# STM32_esc.net
KiCad netlist of a schematic drawn in EAGLE
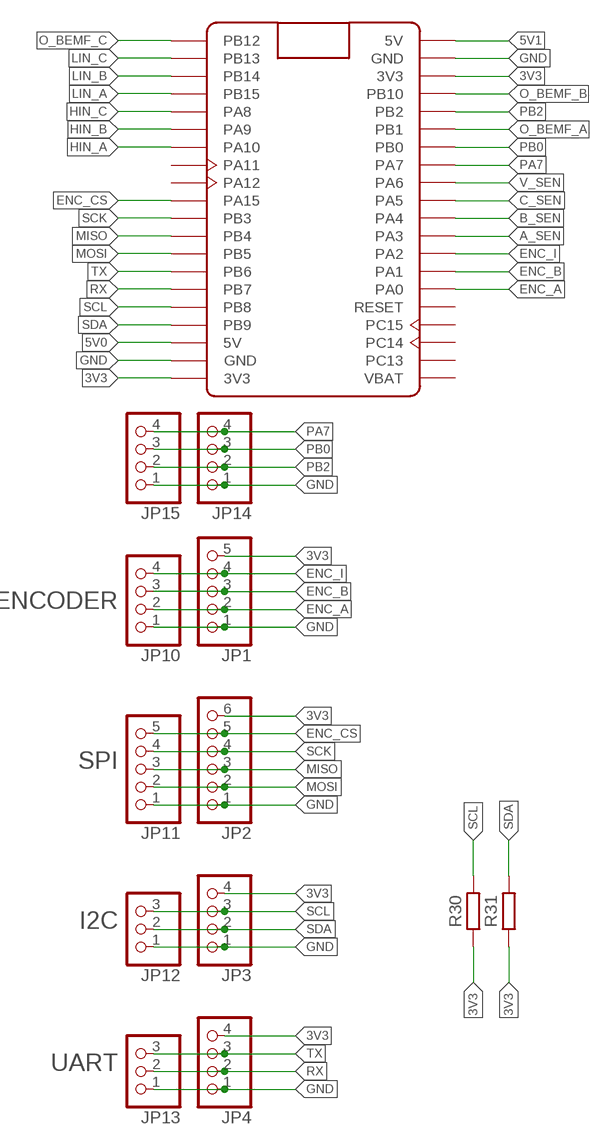
[diagram p0: schematic, sheet 1, part 1 of 2]
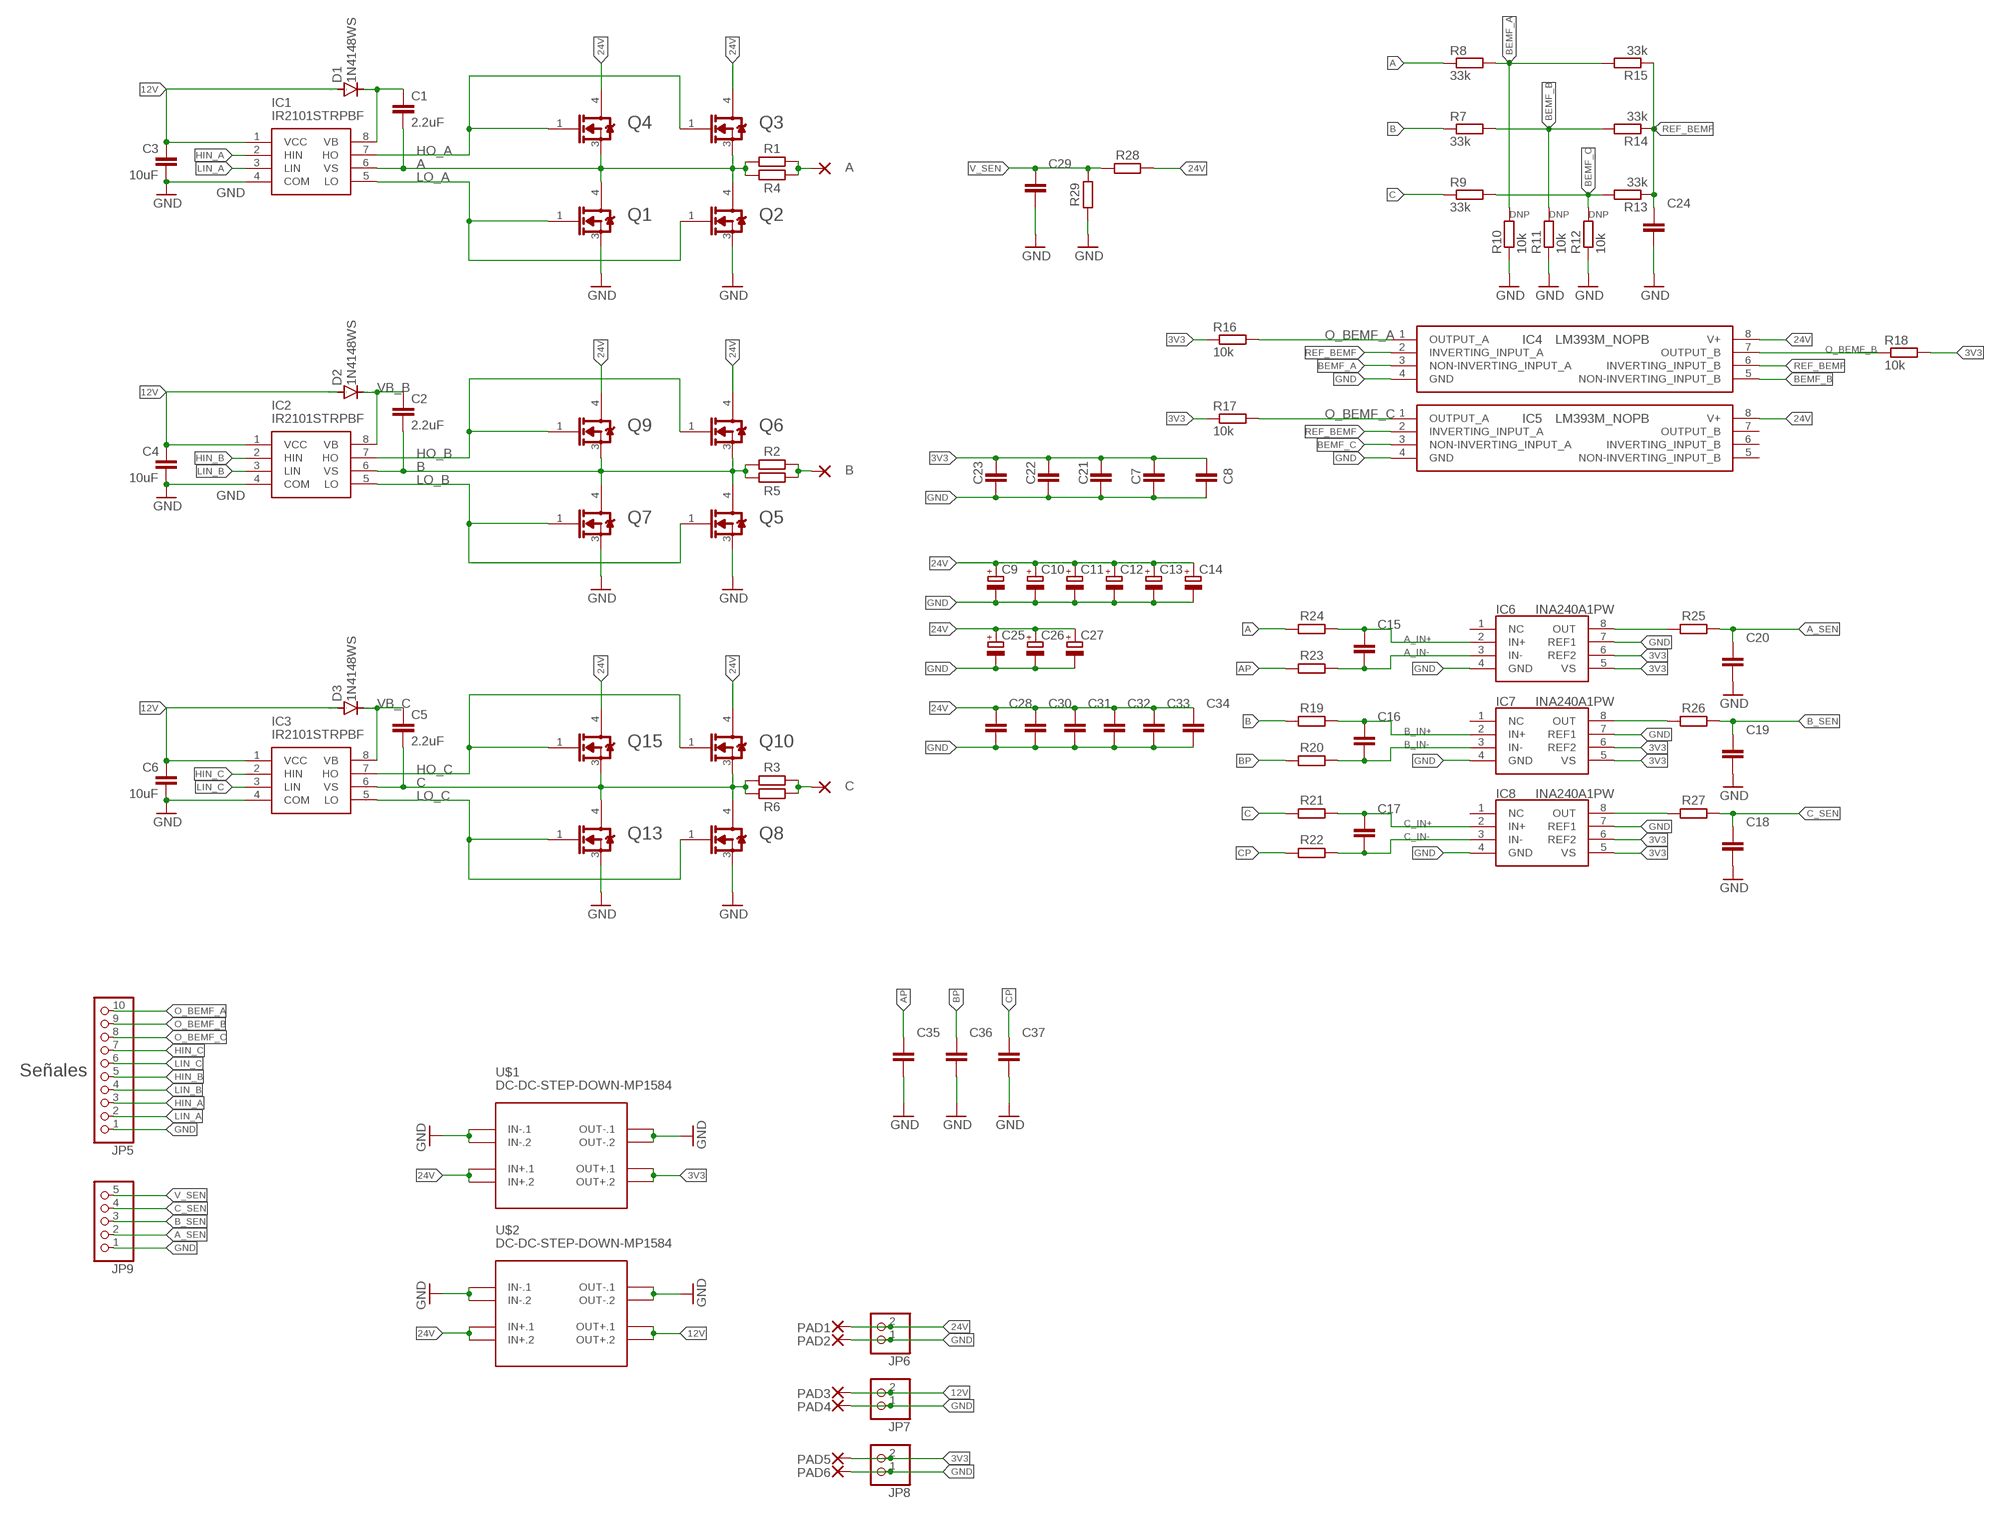
[diagram p1: schematic, sheet 1, part 2 of 2]

(export (version "E")
  (design (tool "Eeschema 10.0.6"))
  (components
    (comp (ref "A")
      (value "SMD5")
      (footprint "eagle-import:SMD2,54-5,08")
      (libsource (lib "eagle-import") (part "SMD5"))
    )
    (comp (ref "B")
      (value "SMD5")
      (footprint "eagle-import:SMD2,54-5,08")
      (libsource (lib "eagle-import") (part "SMD5"))
    )
    (comp (ref "C")
      (value "SMD5")
      (footprint "eagle-import:SMD2,54-5,08")
      (libsource (lib "eagle-import") (part "SMD5"))
    )
    (comp (ref "C1")
      (value "2.2uF")
      (footprint "eagle-import:CAPC3216X135")
      (libsource (lib "eagle-import") (part "CCHIP-1206(3216-METRIC)_"))
    )
    (comp (ref "C2")
      (value "2.2uF")
      (footprint "eagle-import:CAPC3216X135")
      (libsource (lib "eagle-import") (part "CCHIP-1206(3216-METRIC)_"))
    )
    (comp (ref "C3")
      (value "10uF")
      (footprint "eagle-import:CAPC3216X135")
      (libsource (lib "eagle-import") (part "CCHIP-1206(3216-METRIC)_"))
    )
    (comp (ref "C4")
      (value "10uF")
      (footprint "eagle-import:CAPC3216X135")
      (libsource (lib "eagle-import") (part "CCHIP-1206(3216-METRIC)_"))
    )
    (comp (ref "C5")
      (value "2.2uF")
      (footprint "eagle-import:CAPC3216X135")
      (libsource (lib "eagle-import") (part "CCHIP-1206(3216-METRIC)_"))
    )
    (comp (ref "C6")
      (value "10uF")
      (footprint "eagle-import:CAPC3216X135")
      (libsource (lib "eagle-import") (part "CCHIP-1206(3216-METRIC)_"))
    )
    (comp (ref "C7")
      (value "C_CHIP-0603(1608-METRIC)")
      (footprint "eagle-import:0603")
      (libsource (lib "eagle-import") (part "Capacitor_edit_CCHIP-0603(1608-METRIC)_"))
    )
    (comp (ref "C8")
      (value "C_CHIP-0603(1608-METRIC)")
      (footprint "eagle-import:0603")
      (libsource (lib "eagle-import") (part "Capacitor_edit_CCHIP-0603(1608-METRIC)_"))
    )
    (comp (ref "C9")
      (value "C-POL_TANTALUM-2917(7343-METRIC)")
      (footprint "eagle-import:CAPMP7343X310N")
      (libsource (lib "eagle-import") (part "C-POLTANTALUM-2917(7343-METRIC)_"))
    )
    (comp (ref "C10")
      (value "C-POL_TANTALUM-2917(7343-METRIC)")
      (footprint "eagle-import:CAPMP7343X310N")
      (libsource (lib "eagle-import") (part "C-POLTANTALUM-2917(7343-METRIC)_"))
    )
    (comp (ref "C11")
      (value "C-POL_TANTALUM-2917(7343-METRIC)")
      (footprint "eagle-import:CAPMP7343X310N")
      (libsource (lib "eagle-import") (part "C-POLTANTALUM-2917(7343-METRIC)_"))
    )
    (comp (ref "C12")
      (value "C-POL_TANTALUM-2917(7343-METRIC)")
      (footprint "eagle-import:CAPMP7343X310N")
      (libsource (lib "eagle-import") (part "C-POLTANTALUM-2917(7343-METRIC)_"))
    )
    (comp (ref "C13")
      (value "C-POL_TANTALUM-2917(7343-METRIC)")
      (footprint "eagle-import:CAPMP7343X310N")
      (libsource (lib "eagle-import") (part "C-POLTANTALUM-2917(7343-METRIC)_"))
    )
    (comp (ref "C14")
      (value "C-POL_TANTALUM-2917(7343-METRIC)")
      (footprint "eagle-import:CAPMP7343X310N")
      (libsource (lib "eagle-import") (part "C-POLTANTALUM-2917(7343-METRIC)_"))
    )
    (comp (ref "C15")
      (value "C_CHIP-0603(1608-METRIC)")
      (footprint "eagle-import:0603")
      (libsource (lib "eagle-import") (part "Capacitor_edit_CCHIP-0603(1608-METRIC)_"))
    )
    (comp (ref "C16")
      (value "C_CHIP-0603(1608-METRIC)")
      (footprint "eagle-import:0603")
      (libsource (lib "eagle-import") (part "Capacitor_edit_CCHIP-0603(1608-METRIC)_"))
    )
    (comp (ref "C17")
      (value "C_CHIP-0603(1608-METRIC)")
      (footprint "eagle-import:0603")
      (libsource (lib "eagle-import") (part "Capacitor_edit_CCHIP-0603(1608-METRIC)_"))
    )
    (comp (ref "C18")
      (value "C_CHIP-0603(1608-METRIC)")
      (footprint "eagle-import:0603")
      (libsource (lib "eagle-import") (part "Capacitor_edit_CCHIP-0603(1608-METRIC)_"))
    )
    (comp (ref "C19")
      (value "C_CHIP-0603(1608-METRIC)")
      (footprint "eagle-import:0603")
      (libsource (lib "eagle-import") (part "Capacitor_edit_CCHIP-0603(1608-METRIC)_"))
    )
    (comp (ref "C20")
      (value "C_CHIP-0603(1608-METRIC)")
      (footprint "eagle-import:0603")
      (libsource (lib "eagle-import") (part "Capacitor_edit_CCHIP-0603(1608-METRIC)_"))
    )
    (comp (ref "C21")
      (value "C_CHIP-0603(1608-METRIC)")
      (footprint "eagle-import:0603")
      (libsource (lib "eagle-import") (part "Capacitor_edit_CCHIP-0603(1608-METRIC)_"))
    )
    (comp (ref "C22")
      (value "C_CHIP-0603(1608-METRIC)")
      (footprint "eagle-import:0603")
      (libsource (lib "eagle-import") (part "Capacitor_edit_CCHIP-0603(1608-METRIC)_"))
    )
    (comp (ref "C23")
      (value "C_CHIP-0603(1608-METRIC)")
      (footprint "eagle-import:0603")
      (libsource (lib "eagle-import") (part "Capacitor_edit_CCHIP-0603(1608-METRIC)_"))
    )
    (comp (ref "C24")
      (value "C_CHIP-0603(1608-METRIC)")
      (footprint "eagle-import:0603")
      (libsource (lib "eagle-import") (part "Capacitor_edit_CCHIP-0603(1608-METRIC)_"))
    )
    (comp (ref "C25")
      (value "C-POL_ECAP-10.5MM")
      (footprint "eagle-import:CAPAE1030X1050N")
      (libsource (lib "eagle-import") (part "C-POLECAP-10.5MM_"))
    )
    (comp (ref "C26")
      (value "C-POL_ECAP-10.5MM")
      (footprint "eagle-import:CAPAE1030X1050N")
      (libsource (lib "eagle-import") (part "C-POLECAP-10.5MM_"))
    )
    (comp (ref "C27")
      (value "C-POL_ECAP-10.5MM")
      (footprint "eagle-import:CAPAE1030X1050N")
      (libsource (lib "eagle-import") (part "C-POLECAP-10.5MM_"))
    )
    (comp (ref "C28")
      (value "C_CHIP-1206(3216-METRIC)")
      (footprint "eagle-import:1206")
      (libsource (lib "eagle-import") (part "Capacitor_edit_CCHIP-1206(3216-METRIC)_"))
    )
    (comp (ref "C29")
      (value "C_CHIP-0603(1608-METRIC)")
      (footprint "eagle-import:0603")
      (libsource (lib "eagle-import") (part "Capacitor_edit_CCHIP-0603(1608-METRIC)_"))
    )
    (comp (ref "C30")
      (value "C_CHIP-1206(3216-METRIC)")
      (footprint "eagle-import:1206")
      (libsource (lib "eagle-import") (part "Capacitor_edit_CCHIP-1206(3216-METRIC)_"))
    )
    (comp (ref "C31")
      (value "C_CHIP-1206(3216-METRIC)")
      (footprint "eagle-import:1206")
      (libsource (lib "eagle-import") (part "Capacitor_edit_CCHIP-1206(3216-METRIC)_"))
    )
    (comp (ref "C32")
      (value "C_CHIP-1206(3216-METRIC)")
      (footprint "eagle-import:1206")
      (libsource (lib "eagle-import") (part "Capacitor_edit_CCHIP-1206(3216-METRIC)_"))
    )
    (comp (ref "C33")
      (value "C_CHIP-1206(3216-METRIC)")
      (footprint "eagle-import:1206")
      (libsource (lib "eagle-import") (part "Capacitor_edit_CCHIP-1206(3216-METRIC)_"))
    )
    (comp (ref "C34")
      (value "C_CHIP-1206(3216-METRIC)")
      (footprint "eagle-import:1206")
      (libsource (lib "eagle-import") (part "Capacitor_edit_CCHIP-1206(3216-METRIC)_"))
    )
    (comp (ref "C35")
      (value "C_CHIP-1206(3216-METRIC)")
      (footprint "eagle-import:1206")
      (libsource (lib "eagle-import") (part "Capacitor_edit_CCHIP-1206(3216-METRIC)_"))
    )
    (comp (ref "C36")
      (value "C_CHIP-1206(3216-METRIC)")
      (footprint "eagle-import:1206")
      (libsource (lib "eagle-import") (part "Capacitor_edit_CCHIP-1206(3216-METRIC)_"))
    )
    (comp (ref "C37")
      (value "C_CHIP-1206(3216-METRIC)")
      (footprint "eagle-import:1206")
      (libsource (lib "eagle-import") (part "Capacitor_edit_CCHIP-1206(3216-METRIC)_"))
    )
    (comp (ref "D1")
      (value "1N4148WS")
      (footprint "eagle-import:DO35-10")
      (libsource (lib "eagle-import") (part "1N4446"))
    )
    (comp (ref "D2")
      (value "1N4148WS")
      (footprint "eagle-import:DO35-10")
      (libsource (lib "eagle-import") (part "1N4446"))
    )
    (comp (ref "D3")
      (value "1N4148WS")
      (footprint "eagle-import:DO35-10")
      (libsource (lib "eagle-import") (part "1N4446"))
    )
    (comp (ref "IC1")
      (value "IR2101STRPBF")
      (footprint "eagle-import:SOIC127P600X175-8N")
      (fields (field (name "MOUSER_PART_NUMBER") "942-IR2101STRPBF"))
      (libsource (lib "eagle-import") (part "IR2101STRPBF"))
    )
    (comp (ref "IC2")
      (value "IR2101STRPBF")
      (footprint "eagle-import:SOIC127P600X175-8N")
      (fields (field (name "MOUSER_PART_NUMBER") "942-IR2101STRPBF"))
      (libsource (lib "eagle-import") (part "IR2101STRPBF"))
    )
    (comp (ref "IC3")
      (value "IR2101STRPBF")
      (footprint "eagle-import:SOIC127P600X175-8N")
      (fields (field (name "MOUSER_PART_NUMBER") "942-IR2101STRPBF"))
      (libsource (lib "eagle-import") (part "IR2101STRPBF"))
    )
    (comp (ref "IC4")
      (value "LM393M_NOPB")
      (footprint "eagle-import:SOIC127P600X175-8N")
      (fields
        (field (name "ARROW_PART_NUMBER") "LM393M/NOPB")
        (field (name "MOUSER_PART_NUMBER") "926-LM393M/NOPB")
      )
      (libsource (lib "eagle-import") (part "LM393M_NOPB"))
    )
    (comp (ref "IC5")
      (value "LM393M_NOPB")
      (footprint "eagle-import:SOIC127P600X175-8N")
      (fields
        (field (name "ARROW_PART_NUMBER") "LM393M/NOPB")
        (field (name "MOUSER_PART_NUMBER") "926-LM393M/NOPB")
      )
      (libsource (lib "eagle-import") (part "LM393M_NOPB"))
    )
    (comp (ref "IC6")
      (value "INA240A1PW")
      (footprint "eagle-import:SOP65P640X120-8N")
      (fields (field (name "MOUSER_PART_NUMBER") "595-INA240A1PW"))
      (libsource (lib "eagle-import") (part "INA240A1PW"))
    )
    (comp (ref "IC7")
      (value "INA240A1PW")
      (footprint "eagle-import:SOP65P640X120-8N")
      (fields (field (name "MOUSER_PART_NUMBER") "595-INA240A1PW"))
      (libsource (lib "eagle-import") (part "INA240A1PW"))
    )
    (comp (ref "IC8")
      (value "INA240A1PW")
      (footprint "eagle-import:SOP65P640X120-8N")
      (fields (field (name "MOUSER_PART_NUMBER") "595-INA240A1PW"))
      (libsource (lib "eagle-import") (part "INA240A1PW"))
    )
    (comp (ref "JP1")
      (value "PINHD-1X5")
      (footprint "eagle-import:1X05")
      (libsource (lib "eagle-import") (part "PINHD-1X5"))
    )
    (comp (ref "JP2")
      (value "PINHD-1X6")
      (footprint "eagle-import:1X06")
      (libsource (lib "eagle-import") (part "PINHD-1X6"))
    )
    (comp (ref "JP3")
      (value "PINHD-1X4")
      (footprint "eagle-import:1X04")
      (libsource (lib "eagle-import") (part "PINHD-1X4"))
    )
    (comp (ref "JP4")
      (value "PINHD-1X4")
      (footprint "eagle-import:1X04")
      (libsource (lib "eagle-import") (part "PINHD-1X4"))
    )
    (comp (ref "JP5")
      (value "PINHD-1X10")
      (footprint "eagle-import:1X10")
      (libsource (lib "eagle-import") (part "PINHD-1X10"))
    )
    (comp (ref "JP6")
      (value "PINHD-1X2")
      (footprint "eagle-import:1X02")
      (libsource (lib "eagle-import") (part "PINHD-1X2"))
    )
    (comp (ref "JP7")
      (value "PINHD-1X2")
      (footprint "eagle-import:1X02")
      (libsource (lib "eagle-import") (part "PINHD-1X2"))
    )
    (comp (ref "JP8")
      (value "PINHD-1X2")
      (footprint "eagle-import:1X02")
      (libsource (lib "eagle-import") (part "PINHD-1X2"))
    )
    (comp (ref "JP9")
      (value "PINHD-1X5")
      (footprint "eagle-import:1X05")
      (libsource (lib "eagle-import") (part "PINHD-1X5"))
    )
    (comp (ref "JP10")
      (value "PINHD-1X4")
      (footprint "eagle-import:1X04")
      (libsource (lib "eagle-import") (part "PINHD-1X4"))
    )
    (comp (ref "JP11")
      (value "PINHD-1X5")
      (footprint "eagle-import:1X05")
      (libsource (lib "eagle-import") (part "PINHD-1X5"))
    )
    (comp (ref "JP12")
      (value "PINHD-1X3")
      (footprint "eagle-import:1X03")
      (libsource (lib "eagle-import") (part "PINHD-1X3"))
    )
    (comp (ref "JP13")
      (value "PINHD-1X3")
      (footprint "eagle-import:1X03")
      (libsource (lib "eagle-import") (part "PINHD-1X3"))
    )
    (comp (ref "JP14")
      (value "PINHD-1X4")
      (footprint "eagle-import:1X04")
      (libsource (lib "eagle-import") (part "PINHD-1X4"))
    )
    (comp (ref "JP15")
      (value "PINHD-1X4")
      (footprint "eagle-import:1X04")
      (libsource (lib "eagle-import") (part "PINHD-1X4"))
    )
    (comp (ref "PAD1")
      (value "PAD1.27X2.54")
      (footprint "eagle-import:SMD1,27-2,54")
      (libsource (lib "eagle-import") (part "PAD1.27X2.54"))
    )
    (comp (ref "PAD2")
      (value "PAD1.27X2.54")
      (footprint "eagle-import:SMD1,27-2,54")
      (libsource (lib "eagle-import") (part "PAD1.27X2.54"))
    )
    (comp (ref "PAD3")
      (value "PAD1.27X2.54")
      (footprint "eagle-import:SMD1,27-2,54")
      (libsource (lib "eagle-import") (part "PAD1.27X2.54"))
    )
    (comp (ref "PAD4")
      (value "PAD1.27X2.54")
      (footprint "eagle-import:SMD1,27-2,54")
      (libsource (lib "eagle-import") (part "PAD1.27X2.54"))
    )
    (comp (ref "PAD5")
      (value "PAD1.27X2.54")
      (footprint "eagle-import:SMD1,27-2,54")
      (libsource (lib "eagle-import") (part "PAD1.27X2.54"))
    )
    (comp (ref "PAD6")
      (value "PAD1.27X2.54")
      (footprint "eagle-import:SMD1,27-2,54")
      (libsource (lib "eagle-import") (part "PAD1.27X2.54"))
    )
    (comp (ref "Q1")
      (value "INFINEON_IRLR7843TRPBFINFINEON_IRLR7843TRPBF_0_0")
      (footprint "eagle-import:INFINEON_IRLR7843TRPBF_0")
      (fields
        (field (name "DIGIKEY_PART_NUMBER") "IRLR7843PBFCT-ND")
        (field (name "MF") "Infineon")
        (field (name "MOUSER_PART_NUMBER") "942-IRLR7843TRPBF")
      )
      (libsource (lib "eagle-import") (part "INFINEON_IRLR7843TRPBFINFINEON_IRLR7843TRPBF_0_0"))
    )
    (comp (ref "Q2")
      (value "INFINEON_IRLR7843TRPBFINFINEON_IRLR7843TRPBF_0_0")
      (footprint "eagle-import:INFINEON_IRLR7843TRPBF_0")
      (fields
        (field (name "DIGIKEY_PART_NUMBER") "IRLR7843PBFCT-ND")
        (field (name "MF") "Infineon")
        (field (name "MOUSER_PART_NUMBER") "942-IRLR7843TRPBF")
      )
      (libsource (lib "eagle-import") (part "INFINEON_IRLR7843TRPBFINFINEON_IRLR7843TRPBF_0_0"))
    )
    (comp (ref "Q3")
      (value "INFINEON_IRLR7843TRPBFINFINEON_IRLR7843TRPBF_0_0")
      (footprint "eagle-import:INFINEON_IRLR7843TRPBF_0")
      (fields
        (field (name "DIGIKEY_PART_NUMBER") "IRLR7843PBFCT-ND")
        (field (name "MF") "Infineon")
        (field (name "MOUSER_PART_NUMBER") "942-IRLR7843TRPBF")
      )
      (libsource (lib "eagle-import") (part "INFINEON_IRLR7843TRPBFINFINEON_IRLR7843TRPBF_0_0"))
    )
    (comp (ref "Q4")
      (value "INFINEON_IRLR7843TRPBFINFINEON_IRLR7843TRPBF_0_0")
      (footprint "eagle-import:INFINEON_IRLR7843TRPBF_0")
      (fields
        (field (name "DIGIKEY_PART_NUMBER") "IRLR7843PBFCT-ND")
        (field (name "MF") "Infineon")
        (field (name "MOUSER_PART_NUMBER") "942-IRLR7843TRPBF")
      )
      (libsource (lib "eagle-import") (part "INFINEON_IRLR7843TRPBFINFINEON_IRLR7843TRPBF_0_0"))
    )
    (comp (ref "Q5")
      (value "INFINEON_IRLR7843TRPBFINFINEON_IRLR7843TRPBF_0_0")
      (footprint "eagle-import:INFINEON_IRLR7843TRPBF_0")
      (fields
        (field (name "DIGIKEY_PART_NUMBER") "IRLR7843PBFCT-ND")
        (field (name "MF") "Infineon")
        (field (name "MOUSER_PART_NUMBER") "942-IRLR7843TRPBF")
      )
      (libsource (lib "eagle-import") (part "INFINEON_IRLR7843TRPBFINFINEON_IRLR7843TRPBF_0_0"))
    )
    (comp (ref "Q6")
      (value "INFINEON_IRLR7843TRPBFINFINEON_IRLR7843TRPBF_0_0")
      (footprint "eagle-import:INFINEON_IRLR7843TRPBF_0")
      (fields
        (field (name "DIGIKEY_PART_NUMBER") "IRLR7843PBFCT-ND")
        (field (name "MF") "Infineon")
        (field (name "MOUSER_PART_NUMBER") "942-IRLR7843TRPBF")
      )
      (libsource (lib "eagle-import") (part "INFINEON_IRLR7843TRPBFINFINEON_IRLR7843TRPBF_0_0"))
    )
    (comp (ref "Q7")
      (value "INFINEON_IRLR7843TRPBFINFINEON_IRLR7843TRPBF_0_0")
      (footprint "eagle-import:INFINEON_IRLR7843TRPBF_0")
      (fields
        (field (name "DIGIKEY_PART_NUMBER") "IRLR7843PBFCT-ND")
        (field (name "MF") "Infineon")
        (field (name "MOUSER_PART_NUMBER") "942-IRLR7843TRPBF")
      )
      (libsource (lib "eagle-import") (part "INFINEON_IRLR7843TRPBFINFINEON_IRLR7843TRPBF_0_0"))
    )
    (comp (ref "Q8")
      (value "INFINEON_IRLR7843TRPBFINFINEON_IRLR7843TRPBF_0_0")
      (footprint "eagle-import:INFINEON_IRLR7843TRPBF_0")
      (fields
        (field (name "DIGIKEY_PART_NUMBER") "IRLR7843PBFCT-ND")
        (field (name "MF") "Infineon")
        (field (name "MOUSER_PART_NUMBER") "942-IRLR7843TRPBF")
      )
      (libsource (lib "eagle-import") (part "INFINEON_IRLR7843TRPBFINFINEON_IRLR7843TRPBF_0_0"))
    )
    (comp (ref "Q9")
      (value "INFINEON_IRLR7843TRPBFINFINEON_IRLR7843TRPBF_0_0")
      (footprint "eagle-import:INFINEON_IRLR7843TRPBF_0")
      (fields
        (field (name "DIGIKEY_PART_NUMBER") "IRLR7843PBFCT-ND")
        (field (name "MF") "Infineon")
        (field (name "MOUSER_PART_NUMBER") "942-IRLR7843TRPBF")
      )
      (libsource (lib "eagle-import") (part "INFINEON_IRLR7843TRPBFINFINEON_IRLR7843TRPBF_0_0"))
    )
    (comp (ref "Q10")
      (value "INFINEON_IRLR7843TRPBFINFINEON_IRLR7843TRPBF_0_0")
      (footprint "eagle-import:INFINEON_IRLR7843TRPBF_0")
      (fields
        (field (name "DIGIKEY_PART_NUMBER") "IRLR7843PBFCT-ND")
        (field (name "MF") "Infineon")
        (field (name "MOUSER_PART_NUMBER") "942-IRLR7843TRPBF")
      )
      (libsource (lib "eagle-import") (part "INFINEON_IRLR7843TRPBFINFINEON_IRLR7843TRPBF_0_0"))
    )
    (comp (ref "Q13")
      (value "INFINEON_IRLR7843TRPBFINFINEON_IRLR7843TRPBF_0_0")
      (footprint "eagle-import:INFINEON_IRLR7843TRPBF_0")
      (fields
        (field (name "DIGIKEY_PART_NUMBER") "IRLR7843PBFCT-ND")
        (field (name "MF") "Infineon")
        (field (name "MOUSER_PART_NUMBER") "942-IRLR7843TRPBF")
      )
      (libsource (lib "eagle-import") (part "INFINEON_IRLR7843TRPBFINFINEON_IRLR7843TRPBF_0_0"))
    )
    (comp (ref "Q15")
      (value "INFINEON_IRLR7843TRPBFINFINEON_IRLR7843TRPBF_0_0")
      (footprint "eagle-import:INFINEON_IRLR7843TRPBF_0")
      (fields
        (field (name "DIGIKEY_PART_NUMBER") "IRLR7843PBFCT-ND")
        (field (name "MF") "Infineon")
        (field (name "MOUSER_PART_NUMBER") "942-IRLR7843TRPBF")
      )
      (libsource (lib "eagle-import") (part "INFINEON_IRLR7843TRPBFINFINEON_IRLR7843TRPBF_0_0"))
    )
    (comp (ref "R1")
      (value "R_CHIP-2512(6332-METRIC)")
      (footprint "eagle-import:2512")
      (libsource (lib "eagle-import") (part "RCHIP-2512(6332-METRIC)_"))
    )
    (comp (ref "R2")
      (value "R_CHIP-2512(6332-METRIC)")
      (footprint "eagle-import:2512")
      (libsource (lib "eagle-import") (part "RCHIP-2512(6332-METRIC)_"))
    )
    (comp (ref "R3")
      (value "R_CHIP-2512(6332-METRIC)")
      (footprint "eagle-import:2512")
      (libsource (lib "eagle-import") (part "RCHIP-2512(6332-METRIC)_"))
    )
    (comp (ref "R4")
      (value "R_CHIP-2512(6332-METRIC)")
      (footprint "eagle-import:2512")
      (libsource (lib "eagle-import") (part "RCHIP-2512(6332-METRIC)_"))
    )
    (comp (ref "R5")
      (value "R_CHIP-2512(6332-METRIC)")
      (footprint "eagle-import:2512")
      (libsource (lib "eagle-import") (part "RCHIP-2512(6332-METRIC)_"))
    )
    (comp (ref "R6")
      (value "R_CHIP-2512(6332-METRIC)")
      (footprint "eagle-import:2512")
      (libsource (lib "eagle-import") (part "RCHIP-2512(6332-METRIC)_"))
    )
    (comp (ref "R7")
      (value "33k")
      (footprint "eagle-import:0603")
      (libsource (lib "eagle-import") (part "RCHIP-0603(1608-METRIC)_"))
    )
    (comp (ref "R8")
      (value "33k")
      (footprint "eagle-import:0603")
      (libsource (lib "eagle-import") (part "RCHIP-0603(1608-METRIC)_"))
    )
    (comp (ref "R9")
      (value "33k")
      (footprint "eagle-import:0603")
      (libsource (lib "eagle-import") (part "RCHIP-0603(1608-METRIC)_"))
    )
    (comp (ref "R10")
      (value "10k")
      (footprint "eagle-import:0603")
      (libsource (lib "eagle-import") (part "RCHIP-0603(1608-METRIC)_"))
    )
    (comp (ref "R11")
      (value "10k")
      (footprint "eagle-import:0603")
      (libsource (lib "eagle-import") (part "RCHIP-0603(1608-METRIC)_"))
    )
    (comp (ref "R12")
      (value "10k")
      (footprint "eagle-import:0603")
      (libsource (lib "eagle-import") (part "RCHIP-0603(1608-METRIC)_"))
    )
    (comp (ref "R13")
      (value "33k")
      (footprint "eagle-import:0603")
      (libsource (lib "eagle-import") (part "RCHIP-0603(1608-METRIC)_"))
    )
    (comp (ref "R14")
      (value "33k")
      (footprint "eagle-import:0603")
      (libsource (lib "eagle-import") (part "RCHIP-0603(1608-METRIC)_"))
    )
    (comp (ref "R15")
      (value "33k")
      (footprint "eagle-import:0603")
      (libsource (lib "eagle-import") (part "RCHIP-0603(1608-METRIC)_"))
    )
    (comp (ref "R16")
      (value "10k")
      (footprint "eagle-import:0603")
      (libsource (lib "eagle-import") (part "RCHIP-0603(1608-METRIC)_"))
    )
    (comp (ref "R17")
      (value "10k")
      (footprint "eagle-import:0603")
      (libsource (lib "eagle-import") (part "RCHIP-0603(1608-METRIC)_"))
    )
    (comp (ref "R18")
      (value "10k")
      (footprint "eagle-import:0603")
      (libsource (lib "eagle-import") (part "RCHIP-0603(1608-METRIC)_"))
    )
    (comp (ref "R19")
      (value "R_CHIP-0603(1608-METRIC)")
      (footprint "eagle-import:0603")
      (libsource (lib "eagle-import") (part "RCHIP-0603(1608-METRIC)_"))
    )
    (comp (ref "R20")
      (value "R_CHIP-0603(1608-METRIC)")
      (footprint "eagle-import:0603")
      (libsource (lib "eagle-import") (part "RCHIP-0603(1608-METRIC)_"))
    )
    (comp (ref "R21")
      (value "R_CHIP-0603(1608-METRIC)")
      (footprint "eagle-import:0603")
      (libsource (lib "eagle-import") (part "RCHIP-0603(1608-METRIC)_"))
    )
    (comp (ref "R22")
      (value "R_CHIP-0603(1608-METRIC)")
      (footprint "eagle-import:0603")
      (libsource (lib "eagle-import") (part "RCHIP-0603(1608-METRIC)_"))
    )
    (comp (ref "R23")
      (value "R_CHIP-0603(1608-METRIC)")
      (footprint "eagle-import:0603")
      (libsource (lib "eagle-import") (part "RCHIP-0603(1608-METRIC)_"))
    )
    (comp (ref "R24")
      (value "R_CHIP-0603(1608-METRIC)")
      (footprint "eagle-import:0603")
      (libsource (lib "eagle-import") (part "RCHIP-0603(1608-METRIC)_"))
    )
    (comp (ref "R25")
      (value "R_CHIP-0603(1608-METRIC)")
      (footprint "eagle-import:0603")
      (libsource (lib "eagle-import") (part "RCHIP-0603(1608-METRIC)_"))
    )
    (comp (ref "R26")
      (value "R_CHIP-0603(1608-METRIC)")
      (footprint "eagle-import:0603")
      (libsource (lib "eagle-import") (part "RCHIP-0603(1608-METRIC)_"))
    )
    (comp (ref "R27")
      (value "R_CHIP-0603(1608-METRIC)")
      (footprint "eagle-import:0603")
      (libsource (lib "eagle-import") (part "RCHIP-0603(1608-METRIC)_"))
    )
    (comp (ref "R28")
      (value "R_CHIP-0603(1608-METRIC)")
      (footprint "eagle-import:0603")
      (libsource (lib "eagle-import") (part "RCHIP-0603(1608-METRIC)_"))
    )
    (comp (ref "R29")
      (value "R_CHIP-0603(1608-METRIC)")
      (footprint "eagle-import:0603")
      (libsource (lib "eagle-import") (part "RCHIP-0603(1608-METRIC)_"))
    )
    (comp (ref "R30")
      (value "R_CHIP-0603(1608-METRIC)")
      (footprint "eagle-import:0603")
      (libsource (lib "eagle-import") (part "RCHIP-0603(1608-METRIC)_"))
    )
    (comp (ref "R31")
      (value "R_CHIP-0603(1608-METRIC)")
      (footprint "eagle-import:0603")
      (libsource (lib "eagle-import") (part "RCHIP-0603(1608-METRIC)_"))
    )
    (comp (ref "U$1")
      (value "DC-DC-STEP-DOWN-MP1584")
      (footprint "eagle-import:DC-DC-STEP-DOWN-MP1584")
      (libsource (lib "eagle-import") (part "DC-DC-STEP-DOWN-MP1584"))
    )
    (comp (ref "U$2")
      (value "DC-DC-STEP-DOWN-MP1584")
      (footprint "eagle-import:DC-DC-STEP-DOWN-MP1584")
      (libsource (lib "eagle-import") (part "DC-DC-STEP-DOWN-MP1584"))
    )
    (comp (ref "U1")
      (value "STM32F4X1")
      (footprint "eagle-import:BLACK_PILL")
      (libsource (lib "eagle-import") (part "STM32F4X1"))
    )
  )
  (nets
    (net (code "1") (name "/A_IN+") (class "Default")
      (node (ref "C15") (pin "1") (pinfunction "1_1") (pintype "passive"))
      (node (ref "IC6") (pin "2") (pinfunction "IN+_2") (pintype "bidirectional"))
      (node (ref "R24") (pin "2") (pinfunction "2_2") (pintype "passive"))
    )
    (net (code "2") (name "/A_IN-") (class "Default")
      (node (ref "C15") (pin "2") (pinfunction "2_2") (pintype "passive"))
      (node (ref "IC6") (pin "3") (pinfunction "IN-_3") (pintype "bidirectional"))
      (node (ref "R23") (pin "2") (pinfunction "2_2") (pintype "passive"))
    )
    (net (code "3") (name "/B_IN+") (class "Default")
      (node (ref "C16") (pin "1") (pinfunction "1_1") (pintype "passive"))
      (node (ref "IC7") (pin "2") (pinfunction "IN+_2") (pintype "bidirectional"))
      (node (ref "R19") (pin "2") (pinfunction "2_2") (pintype "passive"))
    )
    (net (code "4") (name "/B_IN-") (class "Default")
      (node (ref "C16") (pin "2") (pinfunction "2_2") (pintype "passive"))
      (node (ref "IC7") (pin "3") (pinfunction "IN-_3") (pintype "bidirectional"))
      (node (ref "R20") (pin "2") (pinfunction "2_2") (pintype "passive"))
    )
    (net (code "5") (name "/C_IN+") (class "Default")
      (node (ref "C17") (pin "1") (pinfunction "1_1") (pintype "passive"))
      (node (ref "IC8") (pin "2") (pinfunction "IN+_2") (pintype "bidirectional"))
      (node (ref "R21") (pin "2") (pinfunction "2_2") (pintype "passive"))
    )
    (net (code "6") (name "/C_IN-") (class "Default")
      (node (ref "C17") (pin "2") (pinfunction "2_2") (pintype "passive"))
      (node (ref "IC8") (pin "3") (pinfunction "IN-_3") (pintype "bidirectional"))
      (node (ref "R22") (pin "2") (pinfunction "2_2") (pintype "passive"))
    )
    (net (code "7") (name "/HO_A") (class "Default")
      (node (ref "IC1") (pin "7") (pinfunction "HO_7") (pintype "bidirectional"))
      (node (ref "Q3") (pin "1") (pinfunction "GATE_1") (pintype "passive"))
      (node (ref "Q4") (pin "1") (pinfunction "GATE_1") (pintype "passive"))
    )
    (net (code "8") (name "/HO_B") (class "Default")
      (node (ref "IC2") (pin "7") (pinfunction "HO_7") (pintype "bidirectional"))
      (node (ref "Q6") (pin "1") (pinfunction "GATE_1") (pintype "passive"))
      (node (ref "Q9") (pin "1") (pinfunction "GATE_1") (pintype "passive"))
    )
    (net (code "9") (name "/HO_C") (class "Default")
      (node (ref "IC3") (pin "7") (pinfunction "HO_7") (pintype "bidirectional"))
      (node (ref "Q10") (pin "1") (pinfunction "GATE_1") (pintype "passive"))
      (node (ref "Q15") (pin "1") (pinfunction "GATE_1") (pintype "passive"))
    )
    (net (code "10") (name "/LO_A") (class "Default")
      (node (ref "IC1") (pin "5") (pinfunction "LO_5") (pintype "bidirectional"))
      (node (ref "Q1") (pin "1") (pinfunction "GATE_1") (pintype "passive"))
      (node (ref "Q2") (pin "1") (pinfunction "GATE_1") (pintype "passive"))
    )
    (net (code "11") (name "/LO_B") (class "Default")
      (node (ref "IC2") (pin "5") (pinfunction "LO_5") (pintype "bidirectional"))
      (node (ref "Q5") (pin "1") (pinfunction "GATE_1") (pintype "passive"))
      (node (ref "Q7") (pin "1") (pinfunction "GATE_1") (pintype "passive"))
    )
    (net (code "12") (name "/LO_C") (class "Default")
      (node (ref "IC3") (pin "5") (pinfunction "LO_5") (pintype "bidirectional"))
      (node (ref "Q13") (pin "1") (pinfunction "GATE_1") (pintype "passive"))
      (node (ref "Q8") (pin "1") (pinfunction "GATE_1") (pintype "passive"))
    )
    (net (code "13") (name "/VBAT") (class "Default")
      (node (ref "U1") (pin "P$40") (pinfunction "VBAT_P$40") (pintype "power_in"))
    )
    (net (code "14") (name "/VB_B") (class "Default")
      (node (ref "C2") (pin "1") (pinfunction "1_1") (pintype "passive"))
      (node (ref "D2") (pin "C") (pinfunction "C_C") (pintype "passive"))
      (node (ref "IC2") (pin "8") (pinfunction "VB_8") (pintype "bidirectional"))
    )
    (net (code "15") (name "/VB_C") (class "Default")
      (node (ref "C5") (pin "1") (pinfunction "1_1") (pintype "passive"))
      (node (ref "D3") (pin "C") (pinfunction "C_C") (pintype "passive"))
      (node (ref "IC3") (pin "8") (pinfunction "VB_8") (pintype "bidirectional"))
    )
    (net (code "16") (name "3V3") (class "Default")
      (node (ref "C21") (pin "1") (pinfunction "1_1") (pintype "passive"))
      (node (ref "C22") (pin "1") (pinfunction "1_1") (pintype "passive"))
      (node (ref "C23") (pin "1") (pinfunction "1_1") (pintype "passive"))
      (node (ref "C7") (pin "1") (pinfunction "1_1") (pintype "passive"))
      (node (ref "C8") (pin "1") (pinfunction "1_1") (pintype "passive"))
      (node (ref "IC6") (pin "5") (pinfunction "VS_5") (pintype "bidirectional"))
      (node (ref "IC6") (pin "6") (pinfunction "REF2_6") (pintype "bidirectional"))
      (node (ref "IC7") (pin "5") (pinfunction "VS_5") (pintype "bidirectional"))
      (node (ref "IC7") (pin "6") (pinfunction "REF2_6") (pintype "bidirectional"))
      (node (ref "IC8") (pin "5") (pinfunction "VS_5") (pintype "bidirectional"))
      (node (ref "IC8") (pin "6") (pinfunction "REF2_6") (pintype "bidirectional"))
      (node (ref "JP1") (pin "5") (pinfunction "5_5") (pintype "passive"))
      (node (ref "JP2") (pin "6") (pinfunction "6_6") (pintype "passive"))
      (node (ref "JP3") (pin "4") (pinfunction "4_4") (pintype "passive"))
      (node (ref "JP4") (pin "4") (pinfunction "4_4") (pintype "passive"))
      (node (ref "JP8") (pin "2") (pinfunction "2_2") (pintype "passive"))
      (node (ref "PAD5") (pin "1") (pinfunction "P_1") (pintype "passive"))
      (node (ref "R16") (pin "1") (pinfunction "1_1") (pintype "passive"))
      (node (ref "R17") (pin "1") (pinfunction "1_1") (pintype "passive"))
      (node (ref "R18") (pin "2") (pinfunction "2_2") (pintype "passive"))
      (node (ref "R30") (pin "1") (pinfunction "1_1") (pintype "passive"))
      (node (ref "R31") (pin "1") (pinfunction "1_1") (pintype "passive"))
      (node (ref "U$1") (pin "OUT+.1") (pinfunction "OUT+.1_OUT+.1") (pintype "bidirectional"))
      (node (ref "U$1") (pin "OUT+.2") (pinfunction "OUT+.2_OUT+.2") (pintype "bidirectional"))
      (node (ref "U1") (pin "P$20") (pinfunction "3.3V1_P$20") (pintype "power_in"))
      (node (ref "U1") (pin "P$23") (pinfunction "3V3_P$23") (pintype "power_in"))
    )
    (net (code "17") (name "5V0") (class "Default")
      (node (ref "U1") (pin "P$18") (pinfunction "5V_P$18") (pintype "power_in"))
    )
    (net (code "18") (name "5V1") (class "Default")
      (node (ref "U1") (pin "P$21") (pinfunction "5V0_P$21") (pintype "power_in"))
    )
    (net (code "19") (name "12V") (class "Default")
      (node (ref "C3") (pin "2") (pinfunction "2_2") (pintype "passive"))
      (node (ref "C4") (pin "2") (pinfunction "2_2") (pintype "passive"))
      (node (ref "C6") (pin "2") (pinfunction "2_2") (pintype "passive"))
      (node (ref "D1") (pin "A") (pinfunction "A_A") (pintype "passive"))
      (node (ref "D2") (pin "A") (pinfunction "A_A") (pintype "passive"))
      (node (ref "D3") (pin "A") (pinfunction "A_A") (pintype "passive"))
      (node (ref "IC1") (pin "1") (pinfunction "VCC_1") (pintype "bidirectional"))
      (node (ref "IC2") (pin "1") (pinfunction "VCC_1") (pintype "bidirectional"))
      (node (ref "IC3") (pin "1") (pinfunction "VCC_1") (pintype "bidirectional"))
      (node (ref "JP7") (pin "2") (pinfunction "2_2") (pintype "passive"))
      (node (ref "PAD3") (pin "1") (pinfunction "P_1") (pintype "passive"))
      (node (ref "U$2") (pin "OUT+.1") (pinfunction "OUT+.1_OUT+.1") (pintype "bidirectional"))
      (node (ref "U$2") (pin "OUT+.2") (pinfunction "OUT+.2_OUT+.2") (pintype "bidirectional"))
    )
    (net (code "20") (name "24V") (class "Default")
      (node (ref "C10") (pin "1") (pinfunction "+_1") (pintype "passive"))
      (node (ref "C11") (pin "1") (pinfunction "+_1") (pintype "passive"))
      (node (ref "C12") (pin "1") (pinfunction "+_1") (pintype "passive"))
      (node (ref "C13") (pin "1") (pinfunction "+_1") (pintype "passive"))
      (node (ref "C14") (pin "1") (pinfunction "+_1") (pintype "passive"))
      (node (ref "C25") (pin "1") (pinfunction "+_1") (pintype "passive"))
      (node (ref "C26") (pin "1") (pinfunction "+_1") (pintype "passive"))
      (node (ref "C27") (pin "1") (pinfunction "+_1") (pintype "passive"))
      (node (ref "C28") (pin "1") (pinfunction "1_1") (pintype "passive"))
      (node (ref "C30") (pin "1") (pinfunction "1_1") (pintype "passive"))
      (node (ref "C31") (pin "1") (pinfunction "1_1") (pintype "passive"))
      (node (ref "C32") (pin "1") (pinfunction "1_1") (pintype "passive"))
      (node (ref "C33") (pin "1") (pinfunction "1_1") (pintype "passive"))
      (node (ref "C34") (pin "1") (pinfunction "1_1") (pintype "passive"))
      (node (ref "C9") (pin "1") (pinfunction "+_1") (pintype "passive"))
      (node (ref "IC4") (pin "8") (pinfunction "V+_8") (pintype "bidirectional"))
      (node (ref "IC5") (pin "8") (pinfunction "V+_8") (pintype "bidirectional"))
      (node (ref "JP6") (pin "2") (pinfunction "2_2") (pintype "passive"))
      (node (ref "PAD1") (pin "1") (pinfunction "P_1") (pintype "passive"))
      (node (ref "Q10") (pin "4") (pinfunction "DRAIN_4") (pintype "passive"))
      (node (ref "Q15") (pin "4") (pinfunction "DRAIN_4") (pintype "passive"))
      (node (ref "Q3") (pin "4") (pinfunction "DRAIN_4") (pintype "passive"))
      (node (ref "Q4") (pin "4") (pinfunction "DRAIN_4") (pintype "passive"))
      (node (ref "Q6") (pin "4") (pinfunction "DRAIN_4") (pintype "passive"))
      (node (ref "Q9") (pin "4") (pinfunction "DRAIN_4") (pintype "passive"))
      (node (ref "R28") (pin "2") (pinfunction "2_2") (pintype "passive"))
      (node (ref "U$1") (pin "IN+.1") (pinfunction "IN+.1_IN+.1") (pintype "bidirectional"))
      (node (ref "U$1") (pin "IN+.2") (pinfunction "IN+.2_IN+.2") (pintype "bidirectional"))
      (node (ref "U$2") (pin "IN+.1") (pinfunction "IN+.1_IN+.1") (pintype "bidirectional"))
      (node (ref "U$2") (pin "IN+.2") (pinfunction "IN+.2_IN+.2") (pintype "bidirectional"))
    )
    (net (code "21") (name "A") (class "Default")
      (node (ref "C1") (pin "2") (pinfunction "2_2") (pintype "passive"))
      (node (ref "IC1") (pin "6") (pinfunction "VS_6") (pintype "bidirectional"))
      (node (ref "Q1") (pin "4") (pinfunction "DRAIN_4") (pintype "passive"))
      (node (ref "Q2") (pin "4") (pinfunction "DRAIN_4") (pintype "passive"))
      (node (ref "Q3") (pin "3") (pinfunction "SOURCE_3") (pintype "passive"))
      (node (ref "Q4") (pin "3") (pinfunction "SOURCE_3") (pintype "passive"))
      (node (ref "R1") (pin "1") (pinfunction "1_1") (pintype "passive"))
      (node (ref "R24") (pin "1") (pinfunction "1_1") (pintype "passive"))
      (node (ref "R4") (pin "2") (pinfunction "2_2") (pintype "passive"))
      (node (ref "R8") (pin "1") (pinfunction "1_1") (pintype "passive"))
    )
    (net (code "22") (name "AP") (class "Default")
      (node (ref "A") (pin "1") (pinfunction "P_1") (pintype "passive"))
      (node (ref "C35") (pin "1") (pinfunction "1_1") (pintype "passive"))
      (node (ref "R1") (pin "2") (pinfunction "2_2") (pintype "passive"))
      (node (ref "R23") (pin "1") (pinfunction "1_1") (pintype "passive"))
      (node (ref "R4") (pin "1") (pinfunction "1_1") (pintype "passive"))
    )
    (net (code "23") (name "A_SEN") (class "Default")
      (node (ref "C20") (pin "1") (pinfunction "1_1") (pintype "passive"))
      (node (ref "JP9") (pin "2") (pinfunction "2_2") (pintype "passive"))
      (node (ref "R25") (pin "2") (pinfunction "2_2") (pintype "passive"))
      (node (ref "U1") (pin "P$32") (pinfunction "PA3_P$32") (pintype "bidirectional"))
    )
    (net (code "24") (name "B") (class "Default")
      (node (ref "C2") (pin "2") (pinfunction "2_2") (pintype "passive"))
      (node (ref "IC2") (pin "6") (pinfunction "VS_6") (pintype "bidirectional"))
      (node (ref "Q5") (pin "4") (pinfunction "DRAIN_4") (pintype "passive"))
      (node (ref "Q6") (pin "3") (pinfunction "SOURCE_3") (pintype "passive"))
      (node (ref "Q7") (pin "4") (pinfunction "DRAIN_4") (pintype "passive"))
      (node (ref "Q9") (pin "3") (pinfunction "SOURCE_3") (pintype "passive"))
      (node (ref "R19") (pin "1") (pinfunction "1_1") (pintype "passive"))
      (node (ref "R2") (pin "1") (pinfunction "1_1") (pintype "passive"))
      (node (ref "R5") (pin "2") (pinfunction "2_2") (pintype "passive"))
      (node (ref "R7") (pin "1") (pinfunction "1_1") (pintype "passive"))
    )
    (net (code "25") (name "BEMF_A") (class "Default")
      (node (ref "IC4") (pin "3") (pinfunction "NON-INVERTING_INPUT_A_3") (pintype "bidirectional"))
      (node (ref "R10") (pin "2") (pinfunction "2_2") (pintype "passive"))
      (node (ref "R15") (pin "2") (pinfunction "2_2") (pintype "passive"))
      (node (ref "R8") (pin "2") (pinfunction "2_2") (pintype "passive"))
    )
    (net (code "26") (name "BEMF_B") (class "Default")
      (node (ref "IC4") (pin "5") (pinfunction "NON-INVERTING_INPUT_B_5") (pintype "bidirectional"))
      (node (ref "R11") (pin "2") (pinfunction "2_2") (pintype "passive"))
      (node (ref "R14") (pin "2") (pinfunction "2_2") (pintype "passive"))
      (node (ref "R7") (pin "2") (pinfunction "2_2") (pintype "passive"))
    )
    (net (code "27") (name "BEMF_C") (class "Default")
      (node (ref "IC5") (pin "3") (pinfunction "NON-INVERTING_INPUT_A_3") (pintype "bidirectional"))
      (node (ref "R12") (pin "2") (pinfunction "2_2") (pintype "passive"))
      (node (ref "R13") (pin "2") (pinfunction "2_2") (pintype "passive"))
      (node (ref "R9") (pin "2") (pinfunction "2_2") (pintype "passive"))
    )
    (net (code "28") (name "BP") (class "Default")
      (node (ref "B") (pin "1") (pinfunction "P_1") (pintype "passive"))
      (node (ref "C36") (pin "1") (pinfunction "1_1") (pintype "passive"))
      (node (ref "R2") (pin "2") (pinfunction "2_2") (pintype "passive"))
      (node (ref "R20") (pin "1") (pinfunction "1_1") (pintype "passive"))
      (node (ref "R5") (pin "1") (pinfunction "1_1") (pintype "passive"))
    )
    (net (code "29") (name "B_SEN") (class "Default")
      (node (ref "C19") (pin "1") (pinfunction "1_1") (pintype "passive"))
      (node (ref "JP9") (pin "3") (pinfunction "3_3") (pintype "passive"))
      (node (ref "R26") (pin "2") (pinfunction "2_2") (pintype "passive"))
      (node (ref "U1") (pin "P$31") (pinfunction "PA4_P$31") (pintype "bidirectional"))
    )
    (net (code "30") (name "C") (class "Default")
      (node (ref "C5") (pin "2") (pinfunction "2_2") (pintype "passive"))
      (node (ref "IC3") (pin "6") (pinfunction "VS_6") (pintype "bidirectional"))
      (node (ref "Q10") (pin "3") (pinfunction "SOURCE_3") (pintype "passive"))
      (node (ref "Q13") (pin "4") (pinfunction "DRAIN_4") (pintype "passive"))
      (node (ref "Q15") (pin "3") (pinfunction "SOURCE_3") (pintype "passive"))
      (node (ref "Q8") (pin "4") (pinfunction "DRAIN_4") (pintype "passive"))
      (node (ref "R21") (pin "1") (pinfunction "1_1") (pintype "passive"))
      (node (ref "R3") (pin "1") (pinfunction "1_1") (pintype "passive"))
      (node (ref "R6") (pin "2") (pinfunction "2_2") (pintype "passive"))
      (node (ref "R9") (pin "1") (pinfunction "1_1") (pintype "passive"))
    )
    (net (code "31") (name "CP") (class "Default")
      (node (ref "C") (pin "1") (pinfunction "P_1") (pintype "passive"))
      (node (ref "C37") (pin "1") (pinfunction "1_1") (pintype "passive"))
      (node (ref "R22") (pin "1") (pinfunction "1_1") (pintype "passive"))
      (node (ref "R3") (pin "2") (pinfunction "2_2") (pintype "passive"))
      (node (ref "R6") (pin "1") (pinfunction "1_1") (pintype "passive"))
    )
    (net (code "32") (name "C_SEN") (class "Default")
      (node (ref "C18") (pin "1") (pinfunction "1_1") (pintype "passive"))
      (node (ref "JP9") (pin "4") (pinfunction "4_4") (pintype "passive"))
      (node (ref "R27") (pin "2") (pinfunction "2_2") (pintype "passive"))
      (node (ref "U1") (pin "P$30") (pinfunction "PA5_P$30") (pintype "bidirectional"))
    )
    (net (code "33") (name "ENC_A") (class "Default")
      (node (ref "JP1") (pin "2") (pinfunction "2_2") (pintype "passive"))
      (node (ref "JP10") (pin "2") (pinfunction "2_2") (pintype "passive"))
      (node (ref "U1") (pin "P$35") (pinfunction "PA0_P$35") (pintype "bidirectional"))
    )
    (net (code "34") (name "ENC_B") (class "Default")
      (node (ref "JP1") (pin "3") (pinfunction "3_3") (pintype "passive"))
      (node (ref "JP10") (pin "3") (pinfunction "3_3") (pintype "passive"))
      (node (ref "U1") (pin "P$34") (pinfunction "PA1_P$34") (pintype "bidirectional"))
    )
    (net (code "35") (name "ENC_CS") (class "Default")
      (node (ref "JP11") (pin "5") (pinfunction "5_5") (pintype "passive"))
      (node (ref "JP2") (pin "5") (pinfunction "5_5") (pintype "passive"))
      (node (ref "U1") (pin "P$10") (pinfunction "PA15_P$10") (pintype "bidirectional"))
    )
    (net (code "36") (name "ENC_I") (class "Default")
      (node (ref "JP1") (pin "4") (pinfunction "4_4") (pintype "passive"))
      (node (ref "JP10") (pin "4") (pinfunction "4_4") (pintype "passive"))
      (node (ref "U1") (pin "P$33") (pinfunction "PA2_P$33") (pintype "bidirectional"))
    )
    (net (code "37") (name "GND") (class "Default")
      (node (ref "C10") (pin "2") (pinfunction "-_2") (pintype "passive"))
      (node (ref "C11") (pin "2") (pinfunction "-_2") (pintype "passive"))
      (node (ref "C12") (pin "2") (pinfunction "-_2") (pintype "passive"))
      (node (ref "C13") (pin "2") (pinfunction "-_2") (pintype "passive"))
      (node (ref "C14") (pin "2") (pinfunction "-_2") (pintype "passive"))
      (node (ref "C18") (pin "2") (pinfunction "2_2") (pintype "passive"))
      (node (ref "C19") (pin "2") (pinfunction "2_2") (pintype "passive"))
      (node (ref "C20") (pin "2") (pinfunction "2_2") (pintype "passive"))
      (node (ref "C21") (pin "2") (pinfunction "2_2") (pintype "passive"))
      (node (ref "C22") (pin "2") (pinfunction "2_2") (pintype "passive"))
      (node (ref "C23") (pin "2") (pinfunction "2_2") (pintype "passive"))
      (node (ref "C24") (pin "2") (pinfunction "2_2") (pintype "passive"))
      (node (ref "C25") (pin "2") (pinfunction "-_2") (pintype "passive"))
      (node (ref "C26") (pin "2") (pinfunction "-_2") (pintype "passive"))
      (node (ref "C27") (pin "2") (pinfunction "-_2") (pintype "passive"))
      (node (ref "C28") (pin "2") (pinfunction "2_2") (pintype "passive"))
      (node (ref "C29") (pin "2") (pinfunction "2_2") (pintype "passive"))
      (node (ref "C3") (pin "1") (pinfunction "1_1") (pintype "passive"))
      (node (ref "C30") (pin "2") (pinfunction "2_2") (pintype "passive"))
      (node (ref "C31") (pin "2") (pinfunction "2_2") (pintype "passive"))
      (node (ref "C32") (pin "2") (pinfunction "2_2") (pintype "passive"))
      (node (ref "C33") (pin "2") (pinfunction "2_2") (pintype "passive"))
      (node (ref "C34") (pin "2") (pinfunction "2_2") (pintype "passive"))
      (node (ref "C35") (pin "2") (pinfunction "2_2") (pintype "passive"))
      (node (ref "C36") (pin "2") (pinfunction "2_2") (pintype "passive"))
      (node (ref "C37") (pin "2") (pinfunction "2_2") (pintype "passive"))
      (node (ref "C4") (pin "1") (pinfunction "1_1") (pintype "passive"))
      (node (ref "C6") (pin "1") (pinfunction "1_1") (pintype "passive"))
      (node (ref "C7") (pin "2") (pinfunction "2_2") (pintype "passive"))
      (node (ref "C8") (pin "2") (pinfunction "2_2") (pintype "passive"))
      (node (ref "C9") (pin "2") (pinfunction "-_2") (pintype "passive"))
      (node (ref "IC1") (pin "4") (pinfunction "COM_4") (pintype "bidirectional"))
      (node (ref "IC2") (pin "4") (pinfunction "COM_4") (pintype "bidirectional"))
      (node (ref "IC3") (pin "4") (pinfunction "COM_4") (pintype "bidirectional"))
      (node (ref "IC4") (pin "4") (pinfunction "GND_4") (pintype "bidirectional"))
      (node (ref "IC5") (pin "4") (pinfunction "GND_4") (pintype "bidirectional"))
      (node (ref "IC6") (pin "4") (pinfunction "GND_4") (pintype "bidirectional"))
      (node (ref "IC6") (pin "7") (pinfunction "REF1_7") (pintype "bidirectional"))
      (node (ref "IC7") (pin "4") (pinfunction "GND_4") (pintype "bidirectional"))
      (node (ref "IC7") (pin "7") (pinfunction "REF1_7") (pintype "bidirectional"))
      (node (ref "IC8") (pin "4") (pinfunction "GND_4") (pintype "bidirectional"))
      (node (ref "IC8") (pin "7") (pinfunction "REF1_7") (pintype "bidirectional"))
      (node (ref "JP1") (pin "1") (pinfunction "1_1") (pintype "passive"))
      (node (ref "JP10") (pin "1") (pinfunction "1_1") (pintype "passive"))
      (node (ref "JP11") (pin "1") (pinfunction "1_1") (pintype "passive"))
      (node (ref "JP12") (pin "1") (pinfunction "1_1") (pintype "passive"))
      (node (ref "JP13") (pin "1") (pinfunction "1_1") (pintype "passive"))
      (node (ref "JP14") (pin "1") (pinfunction "1_1") (pintype "passive"))
      (node (ref "JP15") (pin "1") (pinfunction "1_1") (pintype "passive"))
      (node (ref "JP2") (pin "1") (pinfunction "1_1") (pintype "passive"))
      (node (ref "JP3") (pin "1") (pinfunction "1_1") (pintype "passive"))
      (node (ref "JP4") (pin "1") (pinfunction "1_1") (pintype "passive"))
      (node (ref "JP5") (pin "1") (pinfunction "1_1") (pintype "passive"))
      (node (ref "JP6") (pin "1") (pinfunction "1_1") (pintype "passive"))
      (node (ref "JP7") (pin "1") (pinfunction "1_1") (pintype "passive"))
      (node (ref "JP8") (pin "1") (pinfunction "1_1") (pintype "passive"))
      (node (ref "JP9") (pin "1") (pinfunction "1_1") (pintype "passive"))
      (node (ref "PAD2") (pin "1") (pinfunction "P_1") (pintype "passive"))
      (node (ref "PAD4") (pin "1") (pinfunction "P_1") (pintype "passive"))
      (node (ref "PAD6") (pin "1") (pinfunction "P_1") (pintype "passive"))
      (node (ref "Q1") (pin "3") (pinfunction "SOURCE_3") (pintype "passive"))
      (node (ref "Q13") (pin "3") (pinfunction "SOURCE_3") (pintype "passive"))
      (node (ref "Q2") (pin "3") (pinfunction "SOURCE_3") (pintype "passive"))
      (node (ref "Q5") (pin "3") (pinfunction "SOURCE_3") (pintype "passive"))
      (node (ref "Q7") (pin "3") (pinfunction "SOURCE_3") (pintype "passive"))
      (node (ref "Q8") (pin "3") (pinfunction "SOURCE_3") (pintype "passive"))
      (node (ref "R10") (pin "1") (pinfunction "1_1") (pintype "passive"))
      (node (ref "R11") (pin "1") (pinfunction "1_1") (pintype "passive"))
      (node (ref "R12") (pin "1") (pinfunction "1_1") (pintype "passive"))
      (node (ref "R29") (pin "1") (pinfunction "1_1") (pintype "passive"))
      (node (ref "U$1") (pin "IN-.1") (pinfunction "IN-.1_IN-.1") (pintype "bidirectional"))
      (node (ref "U$1") (pin "IN-.2") (pinfunction "IN-.2_IN-.2") (pintype "bidirectional"))
      (node (ref "U$1") (pin "OUT-.1") (pinfunction "OUT-.1_OUT-.1") (pintype "bidirectional"))
      (node (ref "U$1") (pin "OUT-.2") (pinfunction "OUT-.2_OUT-.2") (pintype "bidirectional"))
      (node (ref "U$2") (pin "IN-.1") (pinfunction "IN-.1_IN-.1") (pintype "bidirectional"))
      (node (ref "U$2") (pin "IN-.2") (pinfunction "IN-.2_IN-.2") (pintype "bidirectional"))
      (node (ref "U$2") (pin "OUT-.1") (pinfunction "OUT-.1_OUT-.1") (pintype "bidirectional"))
      (node (ref "U$2") (pin "OUT-.2") (pinfunction "OUT-.2_OUT-.2") (pintype "bidirectional"))
      (node (ref "U1") (pin "P$19") (pinfunction "GND2_P$19") (pintype "power_in"))
      (node (ref "U1") (pin "P$22") (pinfunction "GND_P$22") (pintype "power_in"))
    )
    (net (code "38") (name "HIN_A") (class "Default")
      (node (ref "IC1") (pin "2") (pinfunction "HIN_2") (pintype "bidirectional"))
      (node (ref "JP5") (pin "3") (pinfunction "3_3") (pintype "passive"))
      (node (ref "U1") (pin "P$7") (pinfunction "PA10_P$7") (pintype "bidirectional"))
    )
    (net (code "39") (name "HIN_B") (class "Default")
      (node (ref "IC2") (pin "2") (pinfunction "HIN_2") (pintype "bidirectional"))
      (node (ref "JP5") (pin "5") (pinfunction "5_5") (pintype "passive"))
      (node (ref "U1") (pin "P$6") (pinfunction "PA9_P$6") (pintype "bidirectional"))
    )
    (net (code "40") (name "HIN_C") (class "Default")
      (node (ref "IC3") (pin "2") (pinfunction "HIN_2") (pintype "bidirectional"))
      (node (ref "JP5") (pin "7") (pinfunction "7_7") (pintype "passive"))
      (node (ref "U1") (pin "P$5") (pinfunction "PA8_P$5") (pintype "bidirectional"))
    )
    (net (code "41") (name "LIN_A") (class "Default")
      (node (ref "IC1") (pin "3") (pinfunction "LIN_3") (pintype "bidirectional"))
      (node (ref "JP5") (pin "2") (pinfunction "2_2") (pintype "passive"))
      (node (ref "U1") (pin "P$4") (pinfunction "PB15_P$4") (pintype "bidirectional"))
    )
    (net (code "42") (name "LIN_B") (class "Default")
      (node (ref "IC2") (pin "3") (pinfunction "LIN_3") (pintype "bidirectional"))
      (node (ref "JP5") (pin "4") (pinfunction "4_4") (pintype "passive"))
      (node (ref "U1") (pin "P$3") (pinfunction "PB14_P$3") (pintype "bidirectional"))
    )
    (net (code "43") (name "LIN_C") (class "Default")
      (node (ref "IC3") (pin "3") (pinfunction "LIN_3") (pintype "bidirectional"))
      (node (ref "JP5") (pin "6") (pinfunction "6_6") (pintype "passive"))
      (node (ref "U1") (pin "P$2") (pinfunction "PB13_P$2") (pintype "bidirectional"))
    )
    (net (code "44") (name "MISO") (class "Default")
      (node (ref "JP11") (pin "3") (pinfunction "3_3") (pintype "passive"))
      (node (ref "JP2") (pin "3") (pinfunction "3_3") (pintype "passive"))
      (node (ref "U1") (pin "P$12") (pinfunction "PB4_P$12") (pintype "bidirectional"))
    )
    (net (code "45") (name "MOSI") (class "Default")
      (node (ref "JP11") (pin "2") (pinfunction "2_2") (pintype "passive"))
      (node (ref "JP2") (pin "2") (pinfunction "2_2") (pintype "passive"))
      (node (ref "U1") (pin "P$13") (pinfunction "PB5_P$13") (pintype "bidirectional"))
    )
    (net (code "46") (name "Net-(IC1-VB)") (class "Default")
      (node (ref "C1") (pin "1") (pinfunction "1_1") (pintype "passive"))
      (node (ref "D1") (pin "C") (pinfunction "C_C") (pintype "passive"))
      (node (ref "IC1") (pin "8") (pinfunction "VB_8") (pintype "bidirectional"))
    )
    (net (code "47") (name "Net-(IC6-OUT)") (class "Default")
      (node (ref "IC6") (pin "8") (pinfunction "OUT_8") (pintype "bidirectional"))
      (node (ref "R25") (pin "1") (pinfunction "1_1") (pintype "passive"))
    )
    (net (code "48") (name "Net-(IC7-OUT)") (class "Default")
      (node (ref "IC7") (pin "8") (pinfunction "OUT_8") (pintype "bidirectional"))
      (node (ref "R26") (pin "1") (pinfunction "1_1") (pintype "passive"))
    )
    (net (code "49") (name "Net-(IC8-OUT)") (class "Default")
      (node (ref "IC8") (pin "8") (pinfunction "OUT_8") (pintype "bidirectional"))
      (node (ref "R27") (pin "1") (pinfunction "1_1") (pintype "passive"))
    )
    (net (code "50") (name "O_BEMF_A") (class "Default")
      (node (ref "IC4") (pin "1") (pinfunction "OUTPUT_A_1") (pintype "bidirectional"))
      (node (ref "JP5") (pin "10") (pinfunction "10_10") (pintype "passive"))
      (node (ref "R16") (pin "2") (pinfunction "2_2") (pintype "passive"))
      (node (ref "U1") (pin "P$26") (pinfunction "PB1_P$26") (pintype "bidirectional"))
    )
    (net (code "51") (name "O_BEMF_B") (class "Default")
      (node (ref "IC4") (pin "7") (pinfunction "OUTPUT_B_7") (pintype "bidirectional"))
      (node (ref "JP5") (pin "9") (pinfunction "9_9") (pintype "passive"))
      (node (ref "R18") (pin "1") (pinfunction "1_1") (pintype "passive"))
      (node (ref "U1") (pin "P$24") (pinfunction "PB10_P$24") (pintype "bidirectional"))
    )
    (net (code "52") (name "O_BEMF_C") (class "Default")
      (node (ref "IC5") (pin "1") (pinfunction "OUTPUT_A_1") (pintype "bidirectional"))
      (node (ref "JP5") (pin "8") (pinfunction "8_8") (pintype "passive"))
      (node (ref "R17") (pin "2") (pinfunction "2_2") (pintype "passive"))
      (node (ref "U1") (pin "P$1") (pinfunction "PB12_P$1") (pintype "bidirectional"))
    )
    (net (code "53") (name "PA7") (class "Default")
      (node (ref "JP14") (pin "4") (pinfunction "4_4") (pintype "passive"))
      (node (ref "JP15") (pin "4") (pinfunction "4_4") (pintype "passive"))
      (node (ref "U1") (pin "P$28") (pinfunction "PA7_P$28") (pintype "bidirectional"))
    )
    (net (code "54") (name "PB0") (class "Default")
      (node (ref "JP14") (pin "3") (pinfunction "3_3") (pintype "passive"))
      (node (ref "JP15") (pin "3") (pinfunction "3_3") (pintype "passive"))
      (node (ref "U1") (pin "P$27") (pinfunction "PB0_P$27") (pintype "bidirectional"))
    )
    (net (code "55") (name "PB2") (class "Default")
      (node (ref "JP14") (pin "2") (pinfunction "2_2") (pintype "passive"))
      (node (ref "JP15") (pin "2") (pinfunction "2_2") (pintype "passive"))
      (node (ref "U1") (pin "P$25") (pinfunction "PB2_P$25") (pintype "bidirectional"))
    )
    (net (code "56") (name "REF_BEMF") (class "Default")
      (node (ref "C24") (pin "1") (pinfunction "1_1") (pintype "passive"))
      (node (ref "IC4") (pin "2") (pinfunction "INVERTING_INPUT_A_2") (pintype "bidirectional"))
      (node (ref "IC4") (pin "6") (pinfunction "INVERTING_INPUT_B_6") (pintype "bidirectional"))
      (node (ref "IC5") (pin "2") (pinfunction "INVERTING_INPUT_A_2") (pintype "bidirectional"))
      (node (ref "R13") (pin "1") (pinfunction "1_1") (pintype "passive"))
      (node (ref "R14") (pin "1") (pinfunction "1_1") (pintype "passive"))
      (node (ref "R15") (pin "1") (pinfunction "1_1") (pintype "passive"))
    )
    (net (code "57") (name "RX") (class "Default")
      (node (ref "JP13") (pin "2") (pinfunction "2_2") (pintype "passive"))
      (node (ref "JP4") (pin "2") (pinfunction "2_2") (pintype "passive"))
      (node (ref "U1") (pin "P$15") (pinfunction "PB7_P$15") (pintype "bidirectional"))
    )
    (net (code "58") (name "SCK") (class "Default")
      (node (ref "JP11") (pin "4") (pinfunction "4_4") (pintype "passive"))
      (node (ref "JP2") (pin "4") (pinfunction "4_4") (pintype "passive"))
      (node (ref "U1") (pin "P$11") (pinfunction "PB3_P$11") (pintype "bidirectional"))
    )
    (net (code "59") (name "SCL") (class "Default")
      (node (ref "JP12") (pin "3") (pinfunction "3_3") (pintype "passive"))
      (node (ref "JP3") (pin "3") (pinfunction "3_3") (pintype "passive"))
      (node (ref "R30") (pin "2") (pinfunction "2_2") (pintype "passive"))
      (node (ref "U1") (pin "P$16") (pinfunction "PB8_P$16") (pintype "bidirectional"))
    )
    (net (code "60") (name "SDA") (class "Default")
      (node (ref "JP12") (pin "2") (pinfunction "2_2") (pintype "passive"))
      (node (ref "JP3") (pin "2") (pinfunction "2_2") (pintype "passive"))
      (node (ref "R31") (pin "2") (pinfunction "2_2") (pintype "passive"))
      (node (ref "U1") (pin "P$17") (pinfunction "PB9_P$17") (pintype "bidirectional"))
    )
    (net (code "61") (name "TX") (class "Default")
      (node (ref "JP13") (pin "3") (pinfunction "3_3") (pintype "passive"))
      (node (ref "JP4") (pin "3") (pinfunction "3_3") (pintype "passive"))
      (node (ref "U1") (pin "P$14") (pinfunction "PB6_P$14") (pintype "bidirectional"))
    )
    (net (code "62") (name "V_SEN") (class "Default")
      (node (ref "C29") (pin "1") (pinfunction "1_1") (pintype "passive"))
      (node (ref "JP9") (pin "5") (pinfunction "5_5") (pintype "passive"))
      (node (ref "R28") (pin "1") (pinfunction "1_1") (pintype "passive"))
      (node (ref "R29") (pin "2") (pinfunction "2_2") (pintype "passive"))
      (node (ref "U1") (pin "P$29") (pinfunction "PA6_P$29") (pintype "bidirectional"))
    )
    (net (code "63") (name "unconnected-(IC5-INVERTING_INPUT_B-Pad6)") (class "Default")
      (node (ref "IC5") (pin "6") (pinfunction "INVERTING_INPUT_B_6") (pintype "bidirectional"))
    )
    (net (code "64") (name "unconnected-(IC5-NON-INVERTING_INPUT_B-Pad5)") (class "Default")
      (node (ref "IC5") (pin "5") (pinfunction "NON-INVERTING_INPUT_B_5") (pintype "bidirectional"))
    )
    (net (code "65") (name "unconnected-(IC5-OUTPUT_B-Pad7)") (class "Default")
      (node (ref "IC5") (pin "7") (pinfunction "OUTPUT_B_7") (pintype "bidirectional"))
    )
    (net (code "66") (name "unconnected-(IC6-NC-Pad1)") (class "Default")
      (node (ref "IC6") (pin "1") (pinfunction "NC_1") (pintype "no_connect"))
    )
    (net (code "67") (name "unconnected-(IC7-NC-Pad1)") (class "Default")
      (node (ref "IC7") (pin "1") (pinfunction "NC_1") (pintype "no_connect"))
    )
    (net (code "68") (name "unconnected-(IC8-NC-Pad1)") (class "Default")
      (node (ref "IC8") (pin "1") (pinfunction "NC_1") (pintype "no_connect"))
    )
    (net (code "69") (name "unconnected-(U1-PA11-PadP$8)") (class "Default")
      (node (ref "U1") (pin "P$8") (pinfunction "PA11_P$8") (pintype "no_connect"))
    )
    (net (code "70") (name "unconnected-(U1-PA12-PadP$9)") (class "Default")
      (node (ref "U1") (pin "P$9") (pinfunction "PA12_P$9") (pintype "no_connect"))
    )
    (net (code "71") (name "unconnected-(U1-PC13-PadP$39)") (class "Default")
      (node (ref "U1") (pin "P$39") (pinfunction "PC13_P$39") (pintype "bidirectional"))
    )
    (net (code "72") (name "unconnected-(U1-PC14-PadP$38)") (class "Default")
      (node (ref "U1") (pin "P$38") (pinfunction "PC14_P$38") (pintype "no_connect"))
    )
    (net (code "73") (name "unconnected-(U1-PC15-PadP$37)") (class "Default")
      (node (ref "U1") (pin "P$37") (pinfunction "PC15_P$37") (pintype "no_connect"))
    )
    (net (code "74") (name "unconnected-(U1-RESET-PadP$36)") (class "Default")
      (node (ref "U1") (pin "P$36") (pinfunction "RESET_P$36") (pintype "bidirectional"))
    )
  )
)
